# Processor_Controller.net
KiCad netlist of a schematic drawn in EAGLE
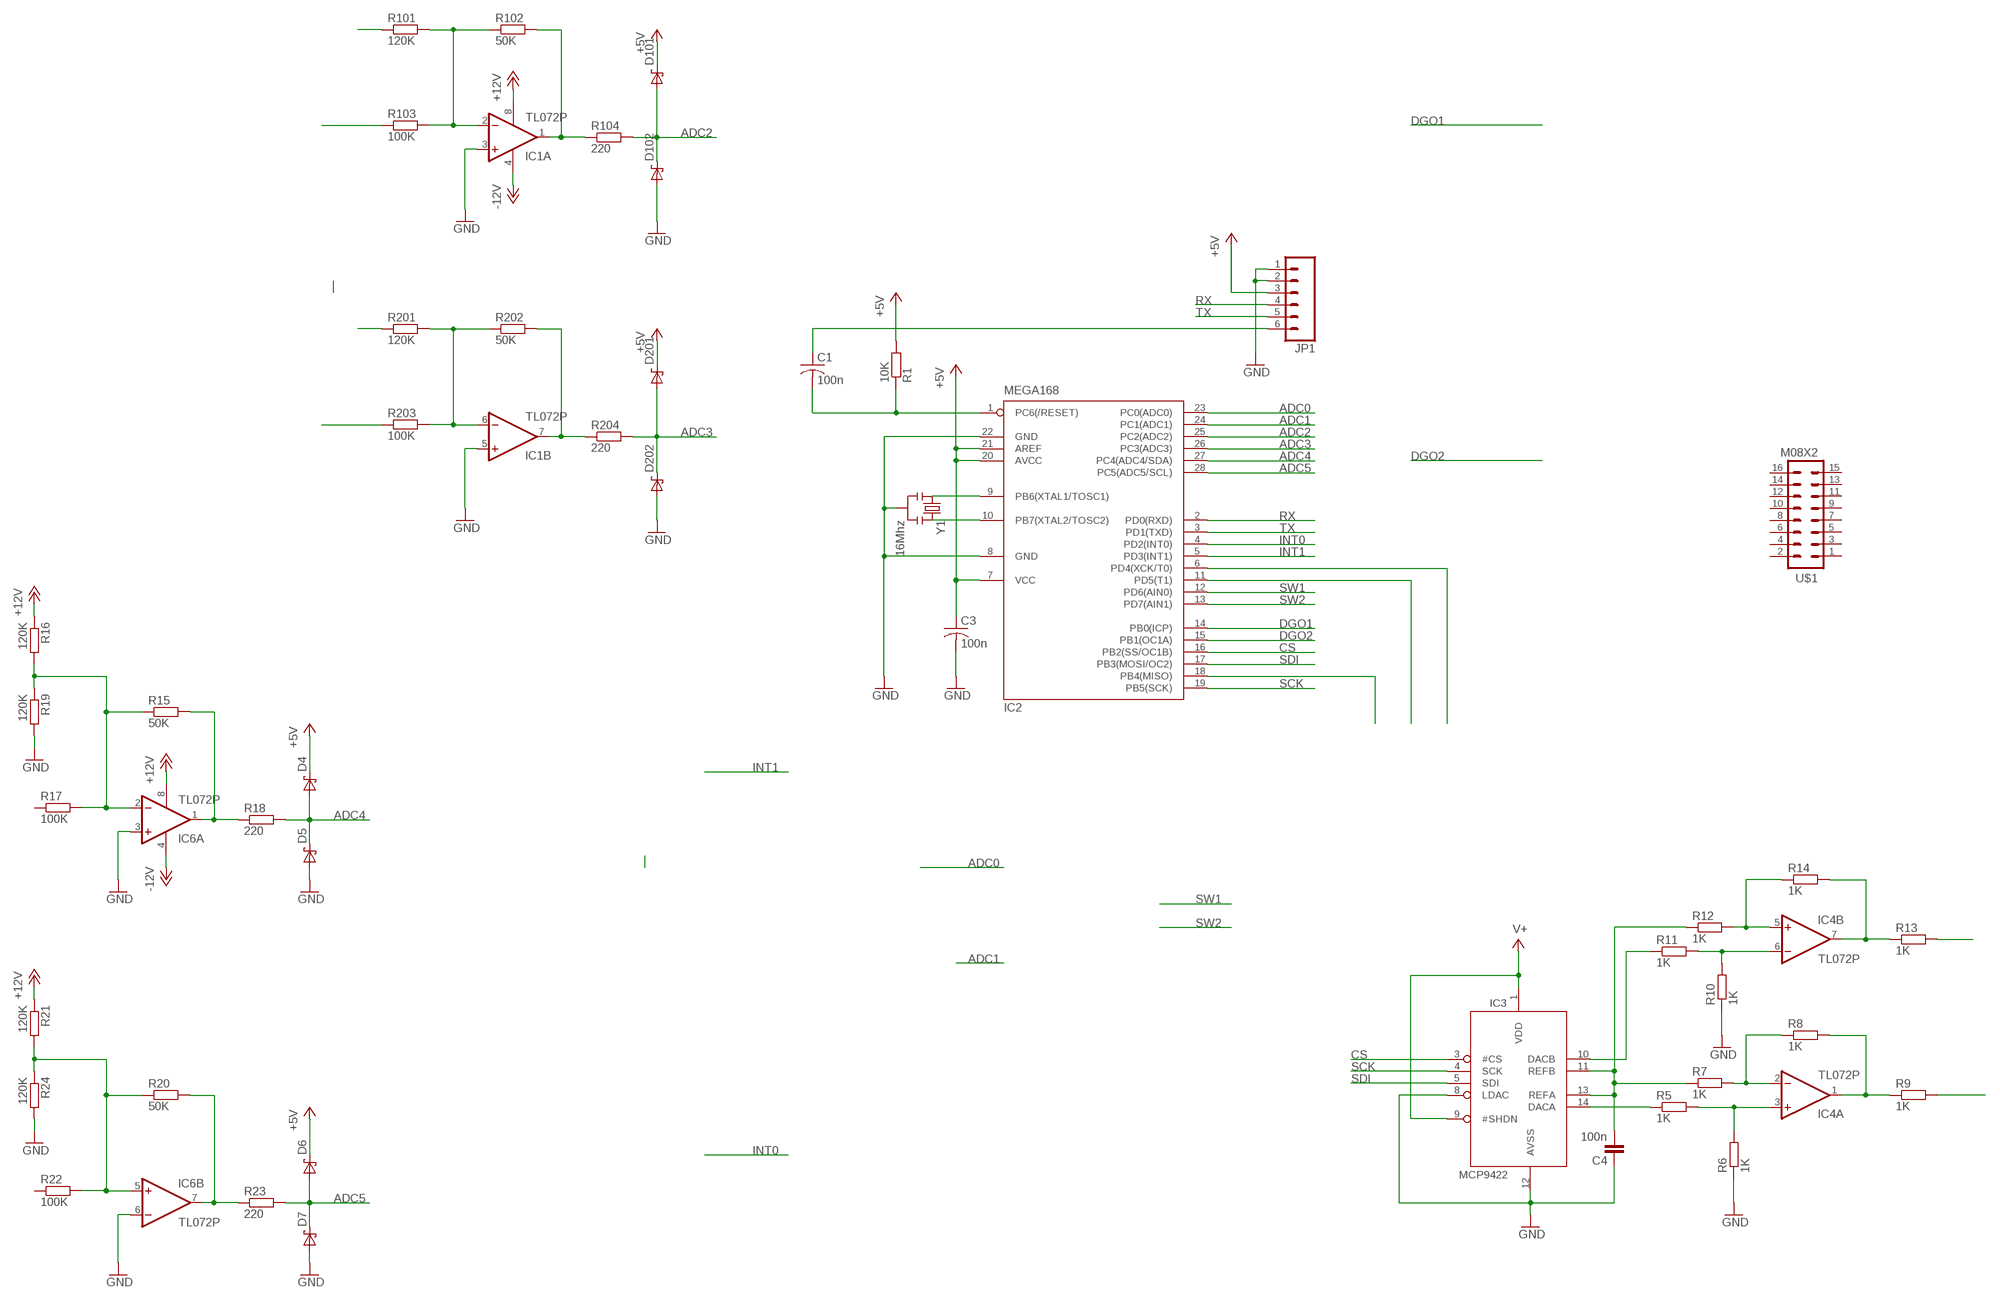
[diagram p0: schematic, sheet 1]

(export (version "E")
  (design (tool "Eeschema 10.0.6"))
  (components
    (comp (ref "C1")
      (value "100n")
      (footprint "eagle-import:C050-024X044")
      (libsource (lib "eagle-import") (part "C-US050-024X044"))
    )
    (comp (ref "C3")
      (value "100n")
      (footprint "eagle-import:C050-024X044")
      (libsource (lib "eagle-import") (part "C-US050-024X044"))
    )
    (comp (ref "C4")
      (value "100n")
      (footprint "eagle-import:C050-030X075")
      (libsource (lib "eagle-import") (part "C-EU050-030X075"))
    )
    (comp (ref "D4")
      (value "DS_E2L")
      (footprint "eagle-import:E2LINE")
      (libsource (lib "eagle-import") (part "DS_E2L"))
    )
    (comp (ref "D5")
      (value "DS_E2L")
      (footprint "eagle-import:E2LINE")
      (fields (field (name "OC_FARNELL") "unknown") (field (name "OC_NEWARK") "unknown"))
      (libsource (lib "eagle-import") (part "DS_E2L"))
    )
    (comp (ref "D6")
      (value "DS_E2L")
      (footprint "eagle-import:E2LINE")
      (libsource (lib "eagle-import") (part "DS_E2L"))
    )
    (comp (ref "D7")
      (value "DS_E2L")
      (footprint "eagle-import:E2LINE")
      (fields (field (name "OC_FARNELL") "unknown") (field (name "OC_NEWARK") "unknown"))
      (libsource (lib "eagle-import") (part "DS_E2L"))
    )
    (comp (ref "D101")
      (value "DS_E2L")
      (footprint "eagle-import:E2LINE")
      (libsource (lib "eagle-import") (part "DS_E2L"))
    )
    (comp (ref "D102")
      (value "DS_E2L")
      (footprint "eagle-import:E2LINE")
      (fields (field (name "OC_FARNELL") "unknown") (field (name "OC_NEWARK") "unknown"))
      (libsource (lib "eagle-import") (part "DS_E2L"))
    )
    (comp (ref "D201")
      (value "DS_E2L")
      (footprint "eagle-import:E2LINE")
      (libsource (lib "eagle-import") (part "DS_E2L"))
    )
    (comp (ref "D202")
      (value "DS_E2L")
      (footprint "eagle-import:E2LINE")
      (fields (field (name "OC_FARNELL") "unknown") (field (name "OC_NEWARK") "unknown"))
      (libsource (lib "eagle-import") (part "DS_E2L"))
    )
    (comp (ref "IC1")
      (value "TL072P")
      (footprint "eagle-import:DIL08")
      (libsource (lib "eagle-import") (part "TL072P"))
    )
    (comp (ref "IC2")
      (value "MEGA168")
      (footprint "eagle-import:DIL28-3")
      (libsource (lib "eagle-import") (part "MEGA8-P"))
    )
    (comp (ref "IC3")
      (value "MCP9422")
      (footprint "eagle-import:DIL14")
      (libsource (lib "eagle-import") (part "MCP9422"))
    )
    (comp (ref "IC4")
      (value "TL072P")
      (footprint "eagle-import:DIL08")
      (libsource (lib "eagle-import") (part "TL072P"))
    )
    (comp (ref "IC6")
      (value "TL072P")
      (footprint "eagle-import:DIL08")
      (libsource (lib "eagle-import") (part "TL072P"))
    )
    (comp (ref "JP1")
      (value "M06SIP")
      (footprint "eagle-import:1X06")
      (libsource (lib "eagle-import") (part "M06SIP"))
    )
    (comp (ref "R1")
      (value "10K")
      (footprint "eagle-import:0204_7")
      (libsource (lib "eagle-import") (part "R-EU_0204/7"))
    )
    (comp (ref "R5")
      (value "1K")
      (footprint "eagle-import:0204_7")
      (libsource (lib "eagle-import") (part "R-EU_0204/7"))
    )
    (comp (ref "R6")
      (value "1K")
      (footprint "eagle-import:0204_7")
      (libsource (lib "eagle-import") (part "R-EU_0204/7"))
    )
    (comp (ref "R7")
      (value "1K")
      (footprint "eagle-import:0204_7")
      (libsource (lib "eagle-import") (part "R-EU_0204/7"))
    )
    (comp (ref "R8")
      (value "1K")
      (footprint "eagle-import:0204_7")
      (libsource (lib "eagle-import") (part "R-EU_0204/7"))
    )
    (comp (ref "R9")
      (value "1K")
      (footprint "eagle-import:0204_7")
      (libsource (lib "eagle-import") (part "R-EU_0204/7"))
    )
    (comp (ref "R10")
      (value "1K")
      (footprint "eagle-import:0204_7")
      (libsource (lib "eagle-import") (part "R-EU_0204/7"))
    )
    (comp (ref "R11")
      (value "1K")
      (footprint "eagle-import:0204_7")
      (libsource (lib "eagle-import") (part "R-EU_0204/7"))
    )
    (comp (ref "R12")
      (value "1K")
      (footprint "eagle-import:0204_7")
      (libsource (lib "eagle-import") (part "R-EU_0204/7"))
    )
    (comp (ref "R13")
      (value "1K")
      (footprint "eagle-import:0204_7")
      (libsource (lib "eagle-import") (part "R-EU_0204/7"))
    )
    (comp (ref "R14")
      (value "1K")
      (footprint "eagle-import:0204_7")
      (libsource (lib "eagle-import") (part "R-EU_0204/7"))
    )
    (comp (ref "R15")
      (value "50K")
      (footprint "eagle-import:0204_7")
      (libsource (lib "eagle-import") (part "resistor_R-EU_0204/7"))
    )
    (comp (ref "R16")
      (value "120K")
      (footprint "eagle-import:0204_7")
      (libsource (lib "eagle-import") (part "resistor_R-EU_0204/7"))
    )
    (comp (ref "R17")
      (value "100K")
      (footprint "eagle-import:0204_7")
      (libsource (lib "eagle-import") (part "resistor_R-EU_0204/7"))
    )
    (comp (ref "R18")
      (value "220")
      (footprint "eagle-import:0204_7")
      (libsource (lib "eagle-import") (part "resistor_R-EU_0204/7"))
    )
    (comp (ref "R19")
      (value "120K")
      (footprint "eagle-import:0204_7")
      (libsource (lib "eagle-import") (part "resistor_R-EU_0204/7"))
    )
    (comp (ref "R20")
      (value "50K")
      (footprint "eagle-import:0204_7")
      (libsource (lib "eagle-import") (part "resistor_R-EU_0204/7"))
    )
    (comp (ref "R21")
      (value "120K")
      (footprint "eagle-import:0204_7")
      (libsource (lib "eagle-import") (part "resistor_R-EU_0204/7"))
    )
    (comp (ref "R22")
      (value "100K")
      (footprint "eagle-import:0204_7")
      (libsource (lib "eagle-import") (part "resistor_R-EU_0204/7"))
    )
    (comp (ref "R23")
      (value "220")
      (footprint "eagle-import:0204_7")
      (libsource (lib "eagle-import") (part "resistor_R-EU_0204/7"))
    )
    (comp (ref "R24")
      (value "120K")
      (footprint "eagle-import:0204_7")
      (libsource (lib "eagle-import") (part "resistor_R-EU_0204/7"))
    )
    (comp (ref "R101")
      (value "120K")
      (footprint "eagle-import:0204_7")
      (libsource (lib "eagle-import") (part "resistor_R-EU_0204/7"))
    )
    (comp (ref "R102")
      (value "50K")
      (footprint "eagle-import:0204_7")
      (libsource (lib "eagle-import") (part "resistor_R-EU_0204/7"))
    )
    (comp (ref "R103")
      (value "100K")
      (footprint "eagle-import:0204_7")
      (libsource (lib "eagle-import") (part "resistor_R-EU_0204/7"))
    )
    (comp (ref "R104")
      (value "220")
      (footprint "eagle-import:0204_7")
      (libsource (lib "eagle-import") (part "resistor_R-EU_0204/7"))
    )
    (comp (ref "R201")
      (value "120K")
      (footprint "eagle-import:0204_7")
      (libsource (lib "eagle-import") (part "resistor_R-EU_0204/7"))
    )
    (comp (ref "R202")
      (value "50K")
      (footprint "eagle-import:0204_7")
      (libsource (lib "eagle-import") (part "resistor_R-EU_0204/7"))
    )
    (comp (ref "R203")
      (value "100K")
      (footprint "eagle-import:0204_7")
      (libsource (lib "eagle-import") (part "resistor_R-EU_0204/7"))
    )
    (comp (ref "R204")
      (value "220")
      (footprint "eagle-import:0204_7")
      (libsource (lib "eagle-import") (part "resistor_R-EU_0204/7"))
    )
    (comp (ref "U$1")
      (value "M08X2")
      (footprint "eagle-import:2X8")
      (libsource (lib "eagle-import") (part "M08X2"))
    )
    (comp (ref "Y1")
      (value "16Mhz")
      (footprint "eagle-import:RESONATOR-PTH")
      (libsource (lib "eagle-import") (part "RESONATORPTH"))
    )
  )
  (nets
    (net (code "1") (name "+5V") (class "Default")
      (node (ref "C3") (pin "1") (pinfunction "1_1") (pintype "passive"))
      (node (ref "D101") (pin "1") (pinfunction "K_1") (pintype "passive"))
      (node (ref "D201") (pin "1") (pinfunction "K_1") (pintype "passive"))
      (node (ref "D4") (pin "1") (pinfunction "K_1") (pintype "passive"))
      (node (ref "D6") (pin "1") (pinfunction "K_1") (pintype "passive"))
      (node (ref "IC2") (pin "20") (pinfunction "AVCC_20") (pintype "power_in"))
      (node (ref "IC2") (pin "21") (pinfunction "AREF_21") (pintype "passive"))
      (node (ref "IC2") (pin "7") (pinfunction "VCC_7") (pintype "power_in"))
      (node (ref "JP1") (pin "3") (pinfunction "3_3") (pintype "passive"))
      (node (ref "R1") (pin "2") (pinfunction "2_2") (pintype "passive"))
    )
    (net (code "2") (name "+12V") (class "Default")
      (node (ref "IC1") (pin "8") (pinfunction "V+_8") (pintype "power_in"))
      (node (ref "IC6") (pin "8") (pinfunction "V+_8") (pintype "power_in"))
      (node (ref "R16") (pin "1") (pinfunction "1_1") (pintype "passive"))
      (node (ref "R21") (pin "1") (pinfunction "1_1") (pintype "passive"))
    )
    (net (code "3") (name "-12V") (class "Default")
      (node (ref "IC1") (pin "4") (pinfunction "V-_4") (pintype "power_in"))
      (node (ref "IC6") (pin "4") (pinfunction "V-_4") (pintype "power_in"))
    )
    (net (code "4") (name "/ADC0") (class "Default")
      (node (ref "IC2") (pin "23") (pinfunction "PC0(ADC0)_23") (pintype "bidirectional"))
    )
    (net (code "5") (name "/ADC1") (class "Default")
      (node (ref "IC2") (pin "24") (pinfunction "PC1(ADC1)_24") (pintype "bidirectional"))
    )
    (net (code "6") (name "/ADC2") (class "Default")
      (node (ref "D101") (pin "2") (pinfunction "A_2") (pintype "passive"))
      (node (ref "D102") (pin "1") (pinfunction "K_1") (pintype "passive"))
      (node (ref "IC2") (pin "25") (pinfunction "PC2(ADC2)_25") (pintype "bidirectional"))
      (node (ref "R104") (pin "2") (pinfunction "2_2") (pintype "passive"))
    )
    (net (code "7") (name "/ADC3") (class "Default")
      (node (ref "D201") (pin "2") (pinfunction "A_2") (pintype "passive"))
      (node (ref "D202") (pin "1") (pinfunction "K_1") (pintype "passive"))
      (node (ref "IC2") (pin "26") (pinfunction "PC3(ADC3)_26") (pintype "bidirectional"))
      (node (ref "R204") (pin "2") (pinfunction "2_2") (pintype "passive"))
    )
    (net (code "8") (name "/ADC4") (class "Default")
      (node (ref "D4") (pin "2") (pinfunction "A_2") (pintype "passive"))
      (node (ref "D5") (pin "1") (pinfunction "K_1") (pintype "passive"))
      (node (ref "IC2") (pin "27") (pinfunction "PC4(ADC4/SDA)_27") (pintype "bidirectional"))
      (node (ref "R18") (pin "2") (pinfunction "2_2") (pintype "passive"))
    )
    (net (code "9") (name "/ADC5") (class "Default")
      (node (ref "D6") (pin "2") (pinfunction "A_2") (pintype "passive"))
      (node (ref "D7") (pin "1") (pinfunction "K_1") (pintype "passive"))
      (node (ref "IC2") (pin "28") (pinfunction "PC5(ADC5/SCL)_28") (pintype "bidirectional"))
      (node (ref "R23") (pin "2") (pinfunction "2_2") (pintype "passive"))
    )
    (net (code "10") (name "/CS") (class "Default")
      (node (ref "IC2") (pin "16") (pinfunction "PB2(SS/OC1B)_16") (pintype "bidirectional"))
      (node (ref "IC3") (pin "3") (pinfunction "#CS_3") (pintype "input"))
    )
    (net (code "11") (name "/DGO1") (class "Default")
      (node (ref "IC2") (pin "14") (pinfunction "PB0(ICP)_14") (pintype "bidirectional"))
    )
    (net (code "12") (name "/DGO2") (class "Default")
      (node (ref "IC2") (pin "15") (pinfunction "PB1(OC1A)_15") (pintype "bidirectional"))
    )
    (net (code "13") (name "/INT0") (class "Default")
      (node (ref "IC2") (pin "4") (pinfunction "PD2(INT0)_4") (pintype "bidirectional"))
    )
    (net (code "14") (name "/INT1") (class "Default")
      (node (ref "IC2") (pin "5") (pinfunction "PD3(INT1)_5") (pintype "bidirectional"))
    )
    (net (code "15") (name "/RX") (class "Default")
      (node (ref "IC2") (pin "2") (pinfunction "PD0(RXD)_2") (pintype "bidirectional"))
      (node (ref "JP1") (pin "4") (pinfunction "4_4") (pintype "passive"))
    )
    (net (code "16") (name "/SCK") (class "Default")
      (node (ref "IC2") (pin "19") (pinfunction "PB5(SCK)_19") (pintype "bidirectional"))
      (node (ref "IC3") (pin "4") (pinfunction "SCK_4") (pintype "input"))
    )
    (net (code "17") (name "/SDI") (class "Default")
      (node (ref "IC2") (pin "17") (pinfunction "PB3(MOSI/OC2)_17") (pintype "bidirectional"))
      (node (ref "IC3") (pin "5") (pinfunction "SDI_5") (pintype "input"))
    )
    (net (code "18") (name "/SW1") (class "Default")
      (node (ref "IC2") (pin "12") (pinfunction "PD6(AIN0)_12") (pintype "bidirectional"))
    )
    (net (code "19") (name "/SW2") (class "Default")
      (node (ref "IC2") (pin "13") (pinfunction "PD7(AIN1)_13") (pintype "bidirectional"))
    )
    (net (code "20") (name "/TX") (class "Default")
      (node (ref "IC2") (pin "3") (pinfunction "PD1(TXD)_3") (pintype "bidirectional"))
      (node (ref "JP1") (pin "5") (pinfunction "5_5") (pintype "passive"))
    )
    (net (code "21") (name "GND") (class "Default")
      (node (ref "C3") (pin "2") (pinfunction "2_2") (pintype "passive"))
      (node (ref "C4") (pin "1") (pinfunction "1_1") (pintype "passive"))
      (node (ref "D102") (pin "2") (pinfunction "A_2") (pintype "passive"))
      (node (ref "D202") (pin "2") (pinfunction "A_2") (pintype "passive"))
      (node (ref "D5") (pin "2") (pinfunction "A_2") (pintype "passive"))
      (node (ref "D7") (pin "2") (pinfunction "A_2") (pintype "passive"))
      (node (ref "IC1") (pin "3") (pinfunction "+IN_3") (pintype "input"))
      (node (ref "IC1") (pin "5") (pinfunction "+IN_5") (pintype "input"))
      (node (ref "IC2") (pin "22") (pinfunction "GND_22") (pintype "power_in"))
      (node (ref "IC2") (pin "8") (pinfunction "GND_8") (pintype "power_in"))
      (node (ref "IC3") (pin "12") (pinfunction "AVSS_12") (pintype "power_in"))
      (node (ref "IC3") (pin "8") (pinfunction "LDAC_8") (pintype "input"))
      (node (ref "IC6") (pin "3") (pinfunction "+IN_3") (pintype "input"))
      (node (ref "IC6") (pin "6") (pinfunction "-IN_6") (pintype "input"))
      (node (ref "JP1") (pin "1") (pinfunction "1_1") (pintype "passive"))
      (node (ref "JP1") (pin "2") (pinfunction "2_2") (pintype "passive"))
      (node (ref "R10") (pin "1") (pinfunction "1_1") (pintype "passive"))
      (node (ref "R19") (pin "2") (pinfunction "2_2") (pintype "passive"))
      (node (ref "R24") (pin "2") (pinfunction "2_2") (pintype "passive"))
      (node (ref "R6") (pin "1") (pinfunction "1_1") (pintype "passive"))
      (node (ref "Y1") (pin "2") (pinfunction "2_2") (pintype "passive"))
    )
    (net (code "22") (name "Net-(C1-Pad1)") (class "Default")
      (node (ref "C1") (pin "1") (pinfunction "1_1") (pintype "passive"))
      (node (ref "JP1") (pin "6") (pinfunction "6_6") (pintype "passive"))
    )
    (net (code "23") (name "Net-(IC1A--IN)") (class "Default")
      (node (ref "IC1") (pin "2") (pinfunction "-IN_2") (pintype "input"))
      (node (ref "R101") (pin "2") (pinfunction "2_2") (pintype "passive"))
      (node (ref "R102") (pin "1") (pinfunction "1_1") (pintype "passive"))
      (node (ref "R103") (pin "2") (pinfunction "2_2") (pintype "passive"))
    )
    (net (code "24") (name "Net-(IC1A-OUT)") (class "Default")
      (node (ref "IC1") (pin "1") (pinfunction "OUT_1") (pintype "output"))
      (node (ref "R102") (pin "2") (pinfunction "2_2") (pintype "passive"))
      (node (ref "R104") (pin "1") (pinfunction "1_1") (pintype "passive"))
    )
    (net (code "25") (name "Net-(IC1B--IN)") (class "Default")
      (node (ref "IC1") (pin "6") (pinfunction "-IN_6") (pintype "input"))
      (node (ref "R201") (pin "2") (pinfunction "2_2") (pintype "passive"))
      (node (ref "R202") (pin "1") (pinfunction "1_1") (pintype "passive"))
      (node (ref "R203") (pin "2") (pinfunction "2_2") (pintype "passive"))
    )
    (net (code "26") (name "Net-(IC1B-OUT)") (class "Default")
      (node (ref "IC1") (pin "7") (pinfunction "OUT_7") (pintype "output"))
      (node (ref "R202") (pin "2") (pinfunction "2_2") (pintype "passive"))
      (node (ref "R204") (pin "1") (pinfunction "1_1") (pintype "passive"))
    )
    (net (code "27") (name "Net-(IC2-PB6(XTAL1{slash}TOSC1))") (class "Default")
      (node (ref "IC2") (pin "9") (pinfunction "PB6(XTAL1/TOSC1)_9") (pintype "bidirectional"))
      (node (ref "Y1") (pin "1") (pinfunction "1_1") (pintype "passive"))
    )
    (net (code "28") (name "Net-(IC2-PB7(XTAL2{slash}TOSC2))") (class "Default")
      (node (ref "IC2") (pin "10") (pinfunction "PB7(XTAL2/TOSC2)_10") (pintype "bidirectional"))
      (node (ref "Y1") (pin "3") (pinfunction "3_3") (pintype "passive"))
    )
    (net (code "29") (name "Net-(IC2-PC6({slash}RESET))") (class "Default")
      (node (ref "C1") (pin "2") (pinfunction "2_2") (pintype "passive"))
      (node (ref "IC2") (pin "1") (pinfunction "PC6(/RESET)_1") (pintype "bidirectional"))
      (node (ref "R1") (pin "1") (pinfunction "1_1") (pintype "passive"))
    )
    (net (code "30") (name "Net-(IC3-DACA)") (class "Default")
      (node (ref "IC3") (pin "14") (pinfunction "DACA_14") (pintype "output"))
      (node (ref "R5") (pin "1") (pinfunction "1_1") (pintype "passive"))
    )
    (net (code "31") (name "Net-(IC3-DACB)") (class "Default")
      (node (ref "IC3") (pin "10") (pinfunction "DACB_10") (pintype "output"))
      (node (ref "R11") (pin "1") (pinfunction "1_1") (pintype "passive"))
    )
    (net (code "32") (name "Net-(IC3-REFA)") (class "Default")
      (node (ref "C4") (pin "2") (pinfunction "2_2") (pintype "passive"))
      (node (ref "IC3") (pin "11") (pinfunction "REFB_11") (pintype "input"))
      (node (ref "IC3") (pin "13") (pinfunction "REFA_13") (pintype "input"))
      (node (ref "R12") (pin "1") (pinfunction "1_1") (pintype "passive"))
      (node (ref "R7") (pin "1") (pinfunction "1_1") (pintype "passive"))
    )
    (net (code "33") (name "Net-(IC4A-+IN)") (class "Default")
      (node (ref "IC4") (pin "3") (pinfunction "+IN_3") (pintype "input"))
      (node (ref "R5") (pin "2") (pinfunction "2_2") (pintype "passive"))
      (node (ref "R6") (pin "2") (pinfunction "2_2") (pintype "passive"))
    )
    (net (code "34") (name "Net-(IC4A--IN)") (class "Default")
      (node (ref "IC4") (pin "2") (pinfunction "-IN_2") (pintype "input"))
      (node (ref "R7") (pin "2") (pinfunction "2_2") (pintype "passive"))
      (node (ref "R8") (pin "1") (pinfunction "1_1") (pintype "passive"))
    )
    (net (code "35") (name "Net-(IC4A-OUT)") (class "Default")
      (node (ref "IC4") (pin "1") (pinfunction "OUT_1") (pintype "output"))
      (node (ref "R8") (pin "2") (pinfunction "2_2") (pintype "passive"))
      (node (ref "R9") (pin "1") (pinfunction "1_1") (pintype "passive"))
    )
    (net (code "36") (name "Net-(IC4B-+IN)") (class "Default")
      (node (ref "IC4") (pin "5") (pinfunction "+IN_5") (pintype "input"))
      (node (ref "R12") (pin "2") (pinfunction "2_2") (pintype "passive"))
      (node (ref "R14") (pin "1") (pinfunction "1_1") (pintype "passive"))
    )
    (net (code "37") (name "Net-(IC4B--IN)") (class "Default")
      (node (ref "IC4") (pin "6") (pinfunction "-IN_6") (pintype "input"))
      (node (ref "R10") (pin "2") (pinfunction "2_2") (pintype "passive"))
      (node (ref "R11") (pin "2") (pinfunction "2_2") (pintype "passive"))
    )
    (net (code "38") (name "Net-(IC4B-OUT)") (class "Default")
      (node (ref "IC4") (pin "7") (pinfunction "OUT_7") (pintype "output"))
      (node (ref "R13") (pin "1") (pinfunction "1_1") (pintype "passive"))
      (node (ref "R14") (pin "2") (pinfunction "2_2") (pintype "passive"))
    )
    (net (code "39") (name "Net-(IC6A--IN)") (class "Default")
      (node (ref "IC6") (pin "2") (pinfunction "-IN_2") (pintype "input"))
      (node (ref "R15") (pin "1") (pinfunction "1_1") (pintype "passive"))
      (node (ref "R16") (pin "2") (pinfunction "2_2") (pintype "passive"))
      (node (ref "R17") (pin "2") (pinfunction "2_2") (pintype "passive"))
      (node (ref "R19") (pin "1") (pinfunction "1_1") (pintype "passive"))
    )
    (net (code "40") (name "Net-(IC6A-OUT)") (class "Default")
      (node (ref "IC6") (pin "1") (pinfunction "OUT_1") (pintype "output"))
      (node (ref "R15") (pin "2") (pinfunction "2_2") (pintype "passive"))
      (node (ref "R18") (pin "1") (pinfunction "1_1") (pintype "passive"))
    )
    (net (code "41") (name "Net-(IC6B-+IN)") (class "Default")
      (node (ref "IC6") (pin "5") (pinfunction "+IN_5") (pintype "input"))
      (node (ref "R20") (pin "1") (pinfunction "1_1") (pintype "passive"))
      (node (ref "R21") (pin "2") (pinfunction "2_2") (pintype "passive"))
      (node (ref "R22") (pin "2") (pinfunction "2_2") (pintype "passive"))
      (node (ref "R24") (pin "1") (pinfunction "1_1") (pintype "passive"))
    )
    (net (code "42") (name "Net-(IC6B-OUT)") (class "Default")
      (node (ref "IC6") (pin "7") (pinfunction "OUT_7") (pintype "output"))
      (node (ref "R20") (pin "2") (pinfunction "2_2") (pintype "passive"))
      (node (ref "R23") (pin "1") (pinfunction "1_1") (pintype "passive"))
    )
    (net (code "43") (name "V+") (class "Default")
      (node (ref "IC3") (pin "1") (pinfunction "VDD_1") (pintype "power_in"))
      (node (ref "IC3") (pin "9") (pinfunction "#SHDN_9") (pintype "input"))
    )
    (net (code "44") (name "unconnected-(IC2-PB4(MISO)-Pad18)") (class "Default")
      (node (ref "IC2") (pin "18") (pinfunction "PB4(MISO)_18") (pintype "bidirectional"))
    )
    (net (code "45") (name "unconnected-(IC2-PD4(XCK{slash}T0)-Pad6)") (class "Default")
      (node (ref "IC2") (pin "6") (pinfunction "PD4(XCK/T0)_6") (pintype "bidirectional"))
    )
    (net (code "46") (name "unconnected-(IC2-PD5(T1)-Pad11)") (class "Default")
      (node (ref "IC2") (pin "11") (pinfunction "PD5(T1)_11") (pintype "bidirectional"))
    )
    (net (code "47") (name "unconnected-(R9-Pad2)") (class "Default")
      (node (ref "R9") (pin "2") (pinfunction "2_2") (pintype "passive"))
    )
    (net (code "48") (name "unconnected-(R13-Pad2)") (class "Default")
      (node (ref "R13") (pin "2") (pinfunction "2_2") (pintype "passive"))
    )
    (net (code "49") (name "unconnected-(R17-Pad1)") (class "Default")
      (node (ref "R17") (pin "1") (pinfunction "1_1") (pintype "passive"))
    )
    (net (code "50") (name "unconnected-(R22-Pad1)") (class "Default")
      (node (ref "R22") (pin "1") (pinfunction "1_1") (pintype "passive"))
    )
    (net (code "51") (name "unconnected-(R101-Pad1)") (class "Default")
      (node (ref "R101") (pin "1") (pinfunction "1_1") (pintype "passive"))
    )
    (net (code "52") (name "unconnected-(R103-Pad1)") (class "Default")
      (node (ref "R103") (pin "1") (pinfunction "1_1") (pintype "passive"))
    )
    (net (code "53") (name "unconnected-(R201-Pad1)") (class "Default")
      (node (ref "R201") (pin "1") (pinfunction "1_1") (pintype "passive"))
    )
    (net (code "54") (name "unconnected-(R203-Pad1)") (class "Default")
      (node (ref "R203") (pin "1") (pinfunction "1_1") (pintype "passive"))
    )
    (net (code "55") (name "unconnected-(U$1-Pad1)") (class "Default")
      (node (ref "U$1") (pin "1") (pinfunction "1_1") (pintype "passive"))
    )
    (net (code "56") (name "unconnected-(U$1-Pad2)") (class "Default")
      (node (ref "U$1") (pin "2") (pinfunction "2_2") (pintype "passive"))
    )
    (net (code "57") (name "unconnected-(U$1-Pad3)") (class "Default")
      (node (ref "U$1") (pin "3") (pinfunction "3_3") (pintype "passive"))
    )
    (net (code "58") (name "unconnected-(U$1-Pad4)") (class "Default")
      (node (ref "U$1") (pin "4") (pinfunction "4_4") (pintype "passive"))
    )
    (net (code "59") (name "unconnected-(U$1-Pad5)") (class "Default")
      (node (ref "U$1") (pin "5") (pinfunction "5_5") (pintype "passive"))
    )
    (net (code "60") (name "unconnected-(U$1-Pad6)") (class "Default")
      (node (ref "U$1") (pin "6") (pinfunction "6_6") (pintype "passive"))
    )
    (net (code "61") (name "unconnected-(U$1-Pad7)") (class "Default")
      (node (ref "U$1") (pin "7") (pinfunction "7_7") (pintype "passive"))
    )
    (net (code "62") (name "unconnected-(U$1-Pad8)") (class "Default")
      (node (ref "U$1") (pin "8") (pinfunction "8_8") (pintype "passive"))
    )
    (net (code "63") (name "unconnected-(U$1-Pad9)") (class "Default")
      (node (ref "U$1") (pin "9") (pinfunction "9_9") (pintype "passive"))
    )
    (net (code "64") (name "unconnected-(U$1-Pad10)") (class "Default")
      (node (ref "U$1") (pin "10") (pinfunction "10_10") (pintype "passive"))
    )
    (net (code "65") (name "unconnected-(U$1-Pad11)") (class "Default")
      (node (ref "U$1") (pin "11") (pinfunction "11_11") (pintype "passive"))
    )
    (net (code "66") (name "unconnected-(U$1-Pad12)") (class "Default")
      (node (ref "U$1") (pin "12") (pinfunction "12_12") (pintype "passive"))
    )
    (net (code "67") (name "unconnected-(U$1-Pad13)") (class "Default")
      (node (ref "U$1") (pin "13") (pinfunction "13_13") (pintype "passive"))
    )
    (net (code "68") (name "unconnected-(U$1-Pad14)") (class "Default")
      (node (ref "U$1") (pin "14") (pinfunction "14_14") (pintype "passive"))
    )
    (net (code "69") (name "unconnected-(U$1-Pad15)") (class "Default")
      (node (ref "U$1") (pin "15") (pinfunction "15_15") (pintype "passive"))
    )
    (net (code "70") (name "unconnected-(U$1-Pad16)") (class "Default")
      (node (ref "U$1") (pin "16") (pinfunction "16_16") (pintype "passive"))
    )
  )
)
